# CtrlCarbinBoard_MCU.net
KiCad netlist of a schematic drawn in Altium Designer
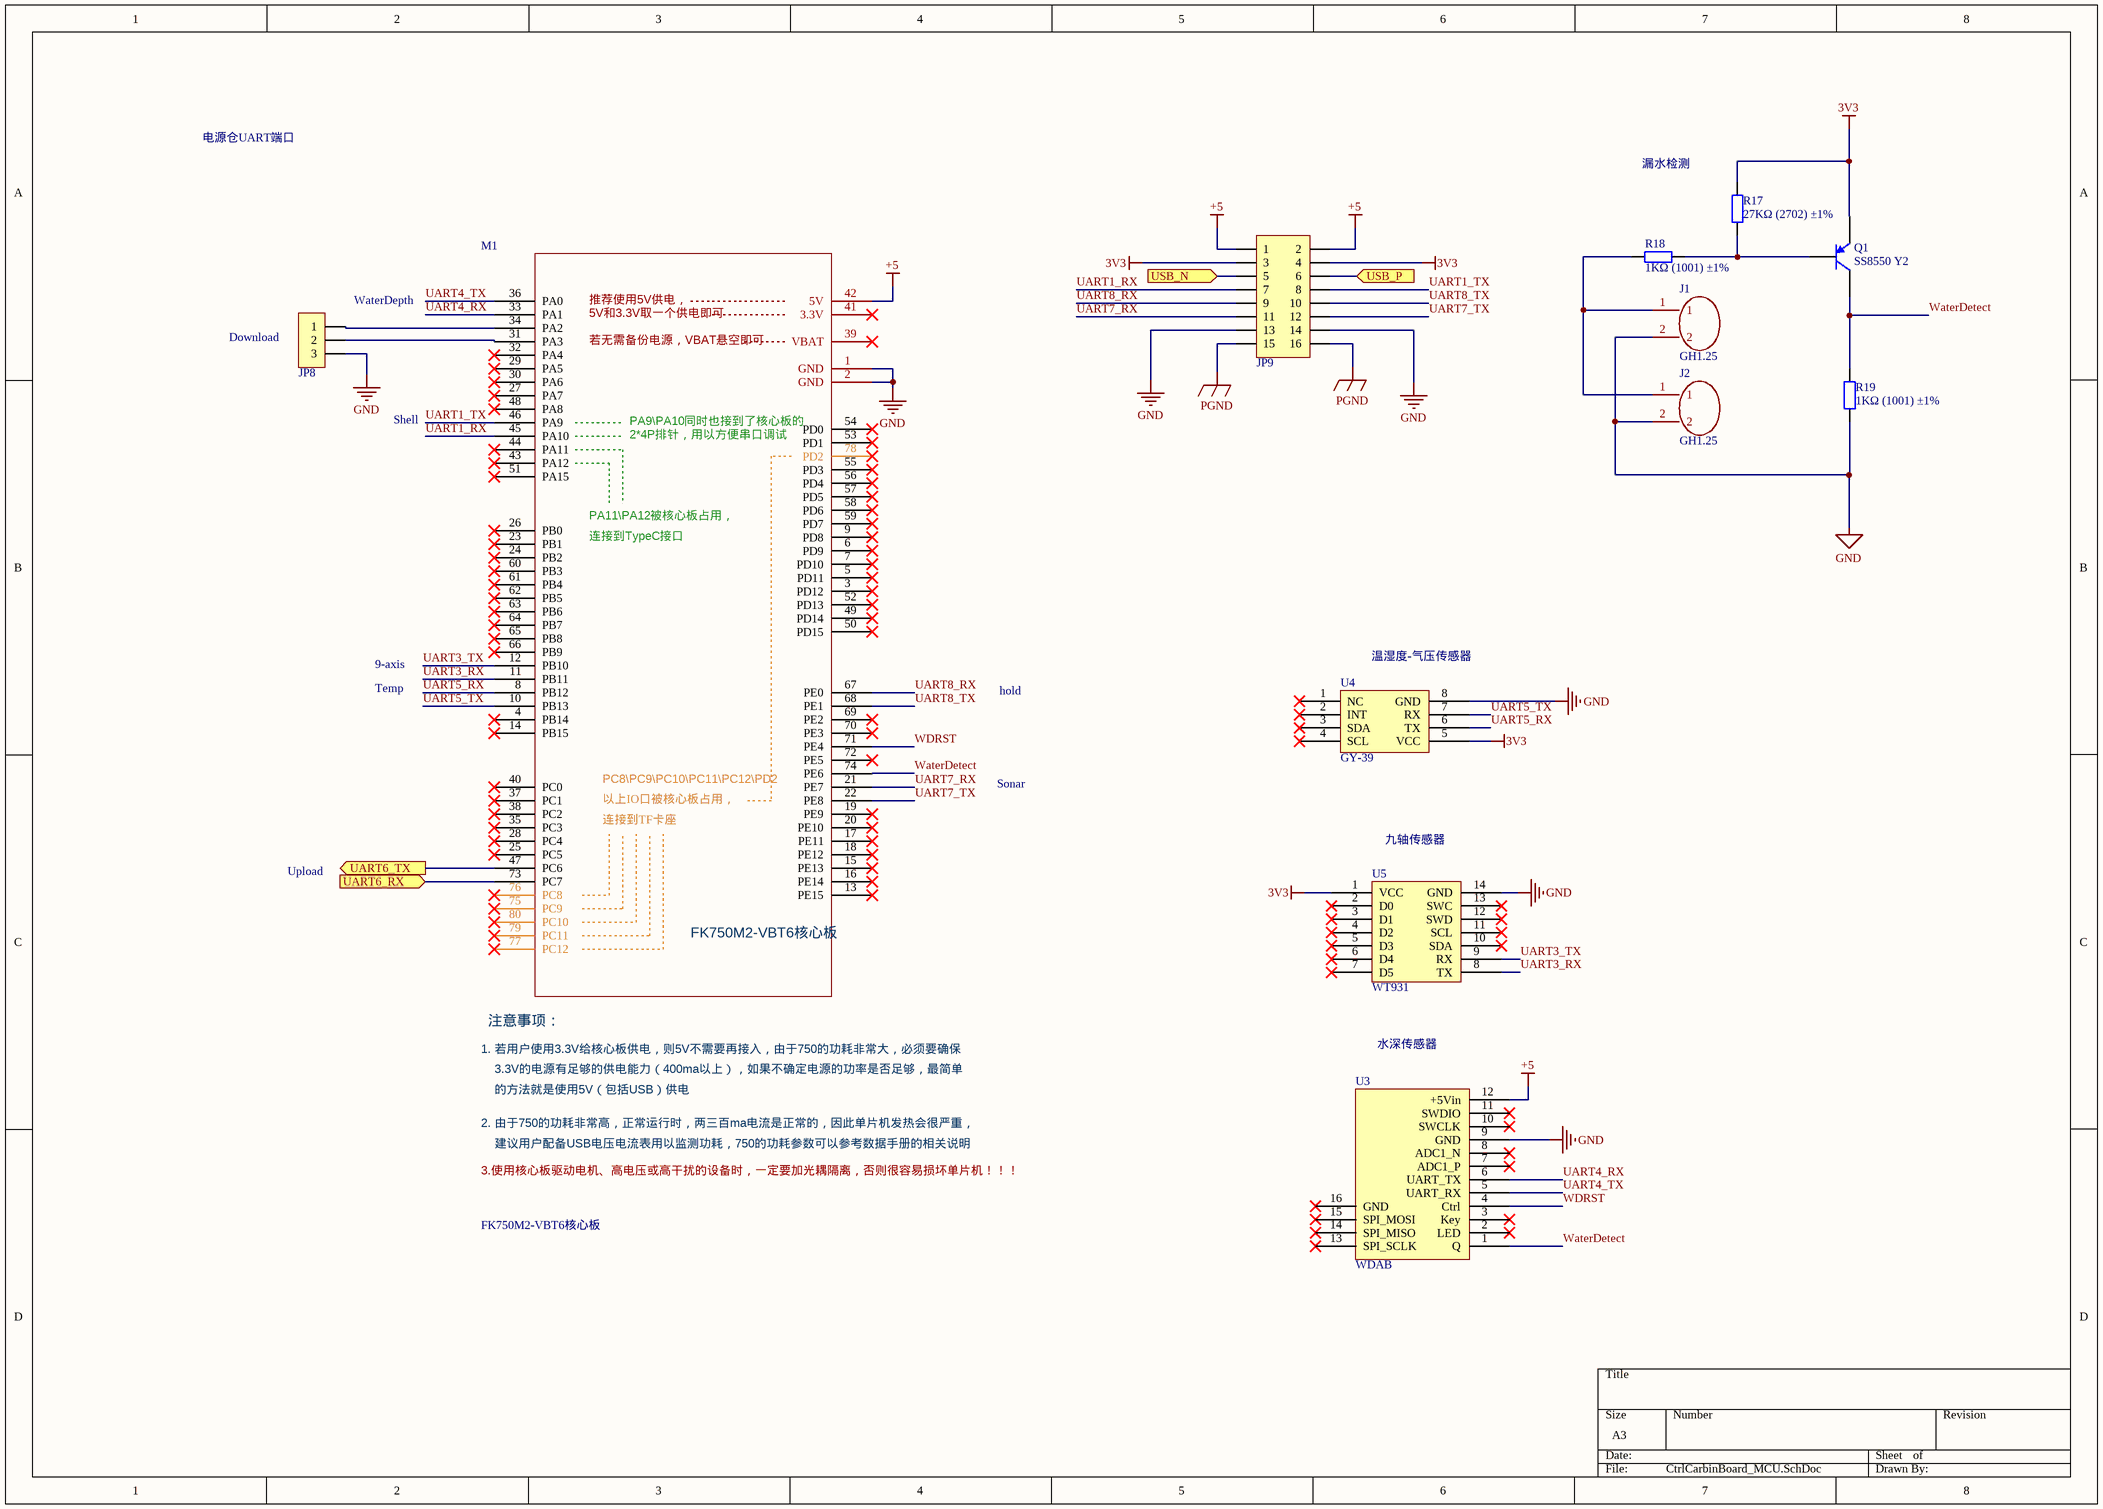
[diagram p0: CtrlCarbinBoard_MCU.SchDoc]

(export (version "E")
  (design (tool "Eeschema 10.0.6"))
  (components
    (comp (ref "J1")
      (value "GH1.25")
      (footprint "GH1.25 2pin")
      (libsource (lib "MySchLib") (part "GH1.25 2pin"))
    )
    (comp (ref "J2")
      (value "GH1.25")
      (footprint "GH1.25 2pin")
      (libsource (lib "MySchLib") (part "GH1.25 2pin"))
    )
    (comp (ref "JP8")
      (value "HDR-1X3")
      (footprint "PH2.0-LS-3P")
      (description "3P接插件")
      (fields (field (name "版权归属") "源创客"))
      (libsource (lib "4.4   - 接插件-脚距2.0") (part "Header 3"))
    )
    (comp (ref "JP9")
      (value "Header 8X2")
      (footprint "IDC2.54-LI-2x8P")
      (description "8*2P接插件")
      (fields (field (name "版权归属") "源创客"))
      (libsource (lib "4.5   - 接插件-脚距2.54") (part "Header 8X2"))
    )
    (comp (ref "M1")
      (value "FK750M2-VBT6核心板")
      (footprint "FK750M2-VBT6(精简版)")
      (libsource (lib "MySchLib") (part "FK750M2-VBT6"))
    )
    (comp (ref "Q1")
      (value "SS8550 Y2")
      (footprint "SOT-23(SOT-23-3)")
      (description "三极管")
      (libsource (lib "Miscellaneous Devices LC") (part "SOT-23 SS8550 Y2"))
    )
    (comp (ref "R17")
      (value "27KΩ (2702) ±1%")
      (footprint "0603_R")
      (description "贴片电阻")
      (libsource (lib "Miscellaneous Devices LC") (part "0603 27KΩ (2702) 1%"))
    )
    (comp (ref "R18")
      (value "1KΩ (1001) ±1%")
      (footprint "0603_R")
      (description "贴片电阻")
      (libsource (lib "") (part "0603 1KΩ (1001) 1%_1"))
    )
    (comp (ref "R19")
      (value "1KΩ (1001) ±1%")
      (footprint "0603_R")
      (description "贴片电阻")
      (libsource (lib "Miscellaneous Devices LC") (part "0603 1KΩ (1001) 1%"))
    )
    (comp (ref "U3")
      (value "WDAB")
      (footprint "WaterDepthBoard")
      (libsource (lib "MySchLib") (part "WaterDepthBoard"))
    )
    (comp (ref "U4")
      (value "GY-39")
      (footprint "GY39")
      (description "GY39温湿度大气压光照传感器")
      (libsource (lib "MySchLib") (part "GY39"))
    )
    (comp (ref "U5")
      (value "WT931")
      (footprint "WT931")
      (description "维特智能WT931九轴模块")
      (libsource (lib "MySchLib") (part "WT931"))
    )
  )
  (nets
    (net (code "1") (name "+5") (class "Default")
      (node (ref "JP9") (pin "1") (pinfunction "1_1") (pintype "passive"))
      (node (ref "JP9") (pin "2") (pinfunction "2_2") (pintype "passive"))
      (node (ref "M1") (pin "42") (pinfunction "5V_42") (pintype "passive"))
      (node (ref "U3") (pin "12") (pinfunction "+5Vin_12") (pintype "passive"))
    )
    (net (code "2") (name "/UART1_RX") (class "Default")
      (node (ref "JP9") (pin "7") (pinfunction "7_7") (pintype "passive"))
      (node (ref "M1") (pin "45") (pinfunction "PA10_45") (pintype "passive"))
    )
    (net (code "3") (name "/UART1_TX") (class "Default")
      (node (ref "JP9") (pin "8") (pinfunction "8_8") (pintype "passive"))
      (node (ref "M1") (pin "46") (pinfunction "PA9_46") (pintype "passive"))
    )
    (net (code "4") (name "/UART3_RX") (class "Default")
      (node (ref "M1") (pin "11") (pinfunction "PB11_11") (pintype "passive"))
      (node (ref "U5") (pin "8") (pinfunction "TX_8") (pintype "passive"))
    )
    (net (code "5") (name "/UART3_TX") (class "Default")
      (node (ref "M1") (pin "12") (pinfunction "PB10_12") (pintype "passive"))
      (node (ref "U5") (pin "9") (pinfunction "RX_9") (pintype "passive"))
    )
    (net (code "6") (name "/UART4_RX") (class "Default")
      (node (ref "M1") (pin "33") (pinfunction "PA1_33") (pintype "passive"))
      (node (ref "U3") (pin "6") (pinfunction "UART_TX_6") (pintype "passive"))
    )
    (net (code "7") (name "/UART4_TX") (class "Default")
      (node (ref "M1") (pin "36") (pinfunction "PA0_36") (pintype "passive"))
      (node (ref "U3") (pin "5") (pinfunction "UART_RX_5") (pintype "passive"))
    )
    (net (code "8") (name "/UART5_RX") (class "Default")
      (node (ref "M1") (pin "8") (pinfunction "PB12_8") (pintype "passive"))
      (node (ref "U4") (pin "6") (pinfunction "TX_6") (pintype "passive"))
    )
    (net (code "9") (name "/UART5_TX") (class "Default")
      (node (ref "M1") (pin "10") (pinfunction "PB13_10") (pintype "passive"))
      (node (ref "U4") (pin "7") (pinfunction "RX_7") (pintype "passive"))
    )
    (net (code "10") (name "/UART6_RX") (class "Default")
      (node (ref "M1") (pin "73") (pinfunction "PC7_73") (pintype "passive"))
    )
    (net (code "11") (name "/UART6_TX") (class "Default")
      (node (ref "M1") (pin "47") (pinfunction "PC6_47") (pintype "passive"))
    )
    (net (code "12") (name "/UART7_RX") (class "Default")
      (node (ref "JP9") (pin "11") (pinfunction "11_11") (pintype "passive"))
      (node (ref "M1") (pin "21") (pinfunction "PE7_21") (pintype "passive"))
    )
    (net (code "13") (name "/UART7_TX") (class "Default")
      (node (ref "JP9") (pin "12") (pinfunction "12_12") (pintype "passive"))
      (node (ref "M1") (pin "22") (pinfunction "PE8_22") (pintype "passive"))
    )
    (net (code "14") (name "/UART8_RX") (class "Default")
      (node (ref "JP9") (pin "9") (pinfunction "9_9") (pintype "passive"))
      (node (ref "M1") (pin "67") (pinfunction "PE0_67") (pintype "passive"))
    )
    (net (code "15") (name "/UART8_TX") (class "Default")
      (node (ref "JP9") (pin "10") (pinfunction "10_10") (pintype "passive"))
      (node (ref "M1") (pin "68") (pinfunction "PE1_68") (pintype "passive"))
    )
    (net (code "16") (name "/USB_N") (class "Default")
      (node (ref "JP9") (pin "5") (pinfunction "5_5") (pintype "passive"))
    )
    (net (code "17") (name "/USB_P") (class "Default")
      (node (ref "JP9") (pin "6") (pinfunction "6_6") (pintype "passive"))
    )
    (net (code "18") (name "/WDRST") (class "Default")
      (node (ref "M1") (pin "71") (pinfunction "PE4_71") (pintype "passive"))
      (node (ref "U3") (pin "4") (pinfunction "Ctrl_4") (pintype "passive"))
    )
    (net (code "19") (name "/WaterDetect") (class "Default")
      (node (ref "M1") (pin "74") (pinfunction "PE6_74") (pintype "passive"))
      (node (ref "Q1") (pin "3") (pinfunction "C_3") (pintype "passive"))
      (node (ref "R19") (pin "2") (pinfunction "2_2") (pintype "passive"))
      (node (ref "U3") (pin "1") (pinfunction "Q_1") (pintype "passive"))
    )
    (net (code "20") (name "3V3") (class "Default")
      (node (ref "JP9") (pin "3") (pinfunction "3_3") (pintype "passive"))
      (node (ref "JP9") (pin "4") (pinfunction "4_4") (pintype "passive"))
      (node (ref "Q1") (pin "2") (pinfunction "E_2") (pintype "passive"))
      (node (ref "R17") (pin "2") (pinfunction "2_2") (pintype "passive"))
      (node (ref "U4") (pin "5") (pinfunction "VCC_5") (pintype "passive"))
      (node (ref "U5") (pin "1") (pinfunction "VCC_1") (pintype "passive"))
    )
    (net (code "21") (name "GND") (class "Default")
      (node (ref "J1") (pin "2") (pinfunction "2_2") (pintype "passive"))
      (node (ref "J2") (pin "2") (pinfunction "2_2") (pintype "passive"))
      (node (ref "JP8") (pin "3") (pinfunction "3_3") (pintype "passive"))
      (node (ref "JP9") (pin "13") (pinfunction "13_13") (pintype "passive"))
      (node (ref "JP9") (pin "14") (pinfunction "14_14") (pintype "passive"))
      (node (ref "M1") (pin "1") (pinfunction "GND_1") (pintype "passive"))
      (node (ref "M1") (pin "2") (pinfunction "GND_2") (pintype "passive"))
      (node (ref "R19") (pin "1") (pinfunction "1_1") (pintype "passive"))
      (node (ref "U3") (pin "9") (pinfunction "GND_9") (pintype "passive"))
      (node (ref "U4") (pin "8") (pinfunction "GND_8") (pintype "passive"))
      (node (ref "U5") (pin "14") (pinfunction "GND_14") (pintype "passive"))
    )
    (net (code "22") (name "Net-(J1-Pad1)") (class "Default")
      (node (ref "J1") (pin "1") (pinfunction "1_1") (pintype "passive"))
      (node (ref "J2") (pin "1") (pinfunction "1_1") (pintype "passive"))
      (node (ref "R18") (pin "1") (pinfunction "1_1") (pintype "passive"))
    )
    (net (code "23") (name "Net-(M1-PA2)") (class "Default")
      (node (ref "JP8") (pin "1") (pinfunction "1_1") (pintype "passive"))
      (node (ref "M1") (pin "34") (pinfunction "PA2_34") (pintype "passive"))
    )
    (net (code "24") (name "Net-(M1-PA3)") (class "Default")
      (node (ref "JP8") (pin "2") (pinfunction "2_2") (pintype "passive"))
      (node (ref "M1") (pin "31") (pinfunction "PA3_31") (pintype "passive"))
    )
    (net (code "25") (name "Net-(Q1-B)") (class "Default")
      (node (ref "Q1") (pin "1") (pinfunction "B_1") (pintype "passive"))
      (node (ref "R17") (pin "1") (pinfunction "1_1") (pintype "passive"))
      (node (ref "R18") (pin "2") (pinfunction "2_2") (pintype "passive"))
    )
    (net (code "26") (name "PGND") (class "Default")
      (node (ref "JP9") (pin "15") (pinfunction "15_15") (pintype "passive"))
      (node (ref "JP9") (pin "16") (pinfunction "16_16") (pintype "passive"))
    )
    (net (code "27") (name "unconnected-(M1-3.3V-Pad41)") (class "Default")
      (node (ref "M1") (pin "41") (pinfunction "3.3V_41") (pintype "passive+no_connect"))
    )
    (net (code "28") (name "unconnected-(M1-PA4-Pad32)") (class "Default")
      (node (ref "M1") (pin "32") (pinfunction "PA4_32") (pintype "passive+no_connect"))
    )
    (net (code "29") (name "unconnected-(M1-PA5-Pad29)") (class "Default")
      (node (ref "M1") (pin "29") (pinfunction "PA5_29") (pintype "passive+no_connect"))
    )
    (net (code "30") (name "unconnected-(M1-PA6-Pad30)") (class "Default")
      (node (ref "M1") (pin "30") (pinfunction "PA6_30") (pintype "passive+no_connect"))
    )
    (net (code "31") (name "unconnected-(M1-PA7-Pad27)") (class "Default")
      (node (ref "M1") (pin "27") (pinfunction "PA7_27") (pintype "passive+no_connect"))
    )
    (net (code "32") (name "unconnected-(M1-PA8-Pad48)") (class "Default")
      (node (ref "M1") (pin "48") (pinfunction "PA8_48") (pintype "passive+no_connect"))
    )
    (net (code "33") (name "unconnected-(M1-PA11-Pad44)") (class "Default")
      (node (ref "M1") (pin "44") (pinfunction "PA11_44") (pintype "passive+no_connect"))
    )
    (net (code "34") (name "unconnected-(M1-PA12-Pad43)") (class "Default")
      (node (ref "M1") (pin "43") (pinfunction "PA12_43") (pintype "passive+no_connect"))
    )
    (net (code "35") (name "unconnected-(M1-PA15-Pad51)") (class "Default")
      (node (ref "M1") (pin "51") (pinfunction "PA15_51") (pintype "passive+no_connect"))
    )
    (net (code "36") (name "unconnected-(M1-PB0-Pad26)") (class "Default")
      (node (ref "M1") (pin "26") (pinfunction "PB0_26") (pintype "passive+no_connect"))
    )
    (net (code "37") (name "unconnected-(M1-PB1-Pad23)") (class "Default")
      (node (ref "M1") (pin "23") (pinfunction "PB1_23") (pintype "passive+no_connect"))
    )
    (net (code "38") (name "unconnected-(M1-PB2-Pad24)") (class "Default")
      (node (ref "M1") (pin "24") (pinfunction "PB2_24") (pintype "passive+no_connect"))
    )
    (net (code "39") (name "unconnected-(M1-PB3-Pad60)") (class "Default")
      (node (ref "M1") (pin "60") (pinfunction "PB3_60") (pintype "passive+no_connect"))
    )
    (net (code "40") (name "unconnected-(M1-PB4-Pad61)") (class "Default")
      (node (ref "M1") (pin "61") (pinfunction "PB4_61") (pintype "passive+no_connect"))
    )
    (net (code "41") (name "unconnected-(M1-PB5-Pad62)") (class "Default")
      (node (ref "M1") (pin "62") (pinfunction "PB5_62") (pintype "passive+no_connect"))
    )
    (net (code "42") (name "unconnected-(M1-PB6-Pad63)") (class "Default")
      (node (ref "M1") (pin "63") (pinfunction "PB6_63") (pintype "passive+no_connect"))
    )
    (net (code "43") (name "unconnected-(M1-PB7-Pad64)") (class "Default")
      (node (ref "M1") (pin "64") (pinfunction "PB7_64") (pintype "passive+no_connect"))
    )
    (net (code "44") (name "unconnected-(M1-PB8-Pad65)") (class "Default")
      (node (ref "M1") (pin "65") (pinfunction "PB8_65") (pintype "passive+no_connect"))
    )
    (net (code "45") (name "unconnected-(M1-PB9-Pad66)") (class "Default")
      (node (ref "M1") (pin "66") (pinfunction "PB9_66") (pintype "passive+no_connect"))
    )
    (net (code "46") (name "unconnected-(M1-PB14-Pad4)") (class "Default")
      (node (ref "M1") (pin "4") (pinfunction "PB14_4") (pintype "passive+no_connect"))
    )
    (net (code "47") (name "unconnected-(M1-PB15-Pad14)") (class "Default")
      (node (ref "M1") (pin "14") (pinfunction "PB15_14") (pintype "passive+no_connect"))
    )
    (net (code "48") (name "unconnected-(M1-PC0-Pad40)") (class "Default")
      (node (ref "M1") (pin "40") (pinfunction "PC0_40") (pintype "passive+no_connect"))
    )
    (net (code "49") (name "unconnected-(M1-PC1-Pad37)") (class "Default")
      (node (ref "M1") (pin "37") (pinfunction "PC1_37") (pintype "passive+no_connect"))
    )
    (net (code "50") (name "unconnected-(M1-PC2-Pad38)") (class "Default")
      (node (ref "M1") (pin "38") (pinfunction "PC2_38") (pintype "passive+no_connect"))
    )
    (net (code "51") (name "unconnected-(M1-PC3-Pad35)") (class "Default")
      (node (ref "M1") (pin "35") (pinfunction "PC3_35") (pintype "passive+no_connect"))
    )
    (net (code "52") (name "unconnected-(M1-PC4-Pad28)") (class "Default")
      (node (ref "M1") (pin "28") (pinfunction "PC4_28") (pintype "passive+no_connect"))
    )
    (net (code "53") (name "unconnected-(M1-PC5-Pad25)") (class "Default")
      (node (ref "M1") (pin "25") (pinfunction "PC5_25") (pintype "passive+no_connect"))
    )
    (net (code "54") (name "unconnected-(M1-PC8-Pad76)") (class "Default")
      (node (ref "M1") (pin "76") (pinfunction "PC8_76") (pintype "passive+no_connect"))
    )
    (net (code "55") (name "unconnected-(M1-PC9-Pad75)") (class "Default")
      (node (ref "M1") (pin "75") (pinfunction "PC9_75") (pintype "passive+no_connect"))
    )
    (net (code "56") (name "unconnected-(M1-PC10-Pad80)") (class "Default")
      (node (ref "M1") (pin "80") (pinfunction "PC10_80") (pintype "passive+no_connect"))
    )
    (net (code "57") (name "unconnected-(M1-PC11-Pad79)") (class "Default")
      (node (ref "M1") (pin "79") (pinfunction "PC11_79") (pintype "passive+no_connect"))
    )
    (net (code "58") (name "unconnected-(M1-PC12-Pad77)") (class "Default")
      (node (ref "M1") (pin "77") (pinfunction "PC12_77") (pintype "passive+no_connect"))
    )
    (net (code "59") (name "unconnected-(M1-PD0-Pad54)") (class "Default")
      (node (ref "M1") (pin "54") (pinfunction "PD0_54") (pintype "passive+no_connect"))
    )
    (net (code "60") (name "unconnected-(M1-PD1-Pad53)") (class "Default")
      (node (ref "M1") (pin "53") (pinfunction "PD1_53") (pintype "passive+no_connect"))
    )
    (net (code "61") (name "unconnected-(M1-PD2-Pad78)") (class "Default")
      (node (ref "M1") (pin "78") (pinfunction "PD2_78") (pintype "passive+no_connect"))
    )
    (net (code "62") (name "unconnected-(M1-PD3-Pad55)") (class "Default")
      (node (ref "M1") (pin "55") (pinfunction "PD3_55") (pintype "passive+no_connect"))
    )
    (net (code "63") (name "unconnected-(M1-PD4-Pad56)") (class "Default")
      (node (ref "M1") (pin "56") (pinfunction "PD4_56") (pintype "passive+no_connect"))
    )
    (net (code "64") (name "unconnected-(M1-PD5-Pad57)") (class "Default")
      (node (ref "M1") (pin "57") (pinfunction "PD5_57") (pintype "passive+no_connect"))
    )
    (net (code "65") (name "unconnected-(M1-PD6-Pad58)") (class "Default")
      (node (ref "M1") (pin "58") (pinfunction "PD6_58") (pintype "passive+no_connect"))
    )
    (net (code "66") (name "unconnected-(M1-PD7-Pad59)") (class "Default")
      (node (ref "M1") (pin "59") (pinfunction "PD7_59") (pintype "passive+no_connect"))
    )
    (net (code "67") (name "unconnected-(M1-PD8-Pad9)") (class "Default")
      (node (ref "M1") (pin "9") (pinfunction "PD8_9") (pintype "passive+no_connect"))
    )
    (net (code "68") (name "unconnected-(M1-PD9-Pad6)") (class "Default")
      (node (ref "M1") (pin "6") (pinfunction "PD9_6") (pintype "passive+no_connect"))
    )
    (net (code "69") (name "unconnected-(M1-PD10-Pad7)") (class "Default")
      (node (ref "M1") (pin "7") (pinfunction "PD10_7") (pintype "passive+no_connect"))
    )
    (net (code "70") (name "unconnected-(M1-PD11-Pad5)") (class "Default")
      (node (ref "M1") (pin "5") (pinfunction "PD11_5") (pintype "passive+no_connect"))
    )
    (net (code "71") (name "unconnected-(M1-PD12-Pad3)") (class "Default")
      (node (ref "M1") (pin "3") (pinfunction "PD12_3") (pintype "passive+no_connect"))
    )
    (net (code "72") (name "unconnected-(M1-PD13-Pad52)") (class "Default")
      (node (ref "M1") (pin "52") (pinfunction "PD13_52") (pintype "passive+no_connect"))
    )
    (net (code "73") (name "unconnected-(M1-PD14-Pad49)") (class "Default")
      (node (ref "M1") (pin "49") (pinfunction "PD14_49") (pintype "passive+no_connect"))
    )
    (net (code "74") (name "unconnected-(M1-PD15-Pad50)") (class "Default")
      (node (ref "M1") (pin "50") (pinfunction "PD15_50") (pintype "passive+no_connect"))
    )
    (net (code "75") (name "unconnected-(M1-PE2-Pad69)") (class "Default")
      (node (ref "M1") (pin "69") (pinfunction "PE2_69") (pintype "passive+no_connect"))
    )
    (net (code "76") (name "unconnected-(M1-PE3-Pad70)") (class "Default")
      (node (ref "M1") (pin "70") (pinfunction "PE3_70") (pintype "passive+no_connect"))
    )
    (net (code "77") (name "unconnected-(M1-PE5-Pad72)") (class "Default")
      (node (ref "M1") (pin "72") (pinfunction "PE5_72") (pintype "passive+no_connect"))
    )
    (net (code "78") (name "unconnected-(M1-PE9-Pad19)") (class "Default")
      (node (ref "M1") (pin "19") (pinfunction "PE9_19") (pintype "passive+no_connect"))
    )
    (net (code "79") (name "unconnected-(M1-PE10-Pad20)") (class "Default")
      (node (ref "M1") (pin "20") (pinfunction "PE10_20") (pintype "passive+no_connect"))
    )
    (net (code "80") (name "unconnected-(M1-PE11-Pad17)") (class "Default")
      (node (ref "M1") (pin "17") (pinfunction "PE11_17") (pintype "passive+no_connect"))
    )
    (net (code "81") (name "unconnected-(M1-PE12-Pad18)") (class "Default")
      (node (ref "M1") (pin "18") (pinfunction "PE12_18") (pintype "passive+no_connect"))
    )
    (net (code "82") (name "unconnected-(M1-PE13-Pad15)") (class "Default")
      (node (ref "M1") (pin "15") (pinfunction "PE13_15") (pintype "passive+no_connect"))
    )
    (net (code "83") (name "unconnected-(M1-PE14-Pad16)") (class "Default")
      (node (ref "M1") (pin "16") (pinfunction "PE14_16") (pintype "passive+no_connect"))
    )
    (net (code "84") (name "unconnected-(M1-PE15-Pad13)") (class "Default")
      (node (ref "M1") (pin "13") (pinfunction "PE15_13") (pintype "passive+no_connect"))
    )
    (net (code "85") (name "unconnected-(M1-VBAT-Pad39)") (class "Default")
      (node (ref "M1") (pin "39") (pinfunction "VBAT_39") (pintype "passive+no_connect"))
    )
    (net (code "86") (name "unconnected-(U3-ADC1_N-Pad8)") (class "Default")
      (node (ref "U3") (pin "8") (pinfunction "ADC1_N_8") (pintype "passive+no_connect"))
    )
    (net (code "87") (name "unconnected-(U3-ADC1_P-Pad7)") (class "Default")
      (node (ref "U3") (pin "7") (pinfunction "ADC1_P_7") (pintype "passive+no_connect"))
    )
    (net (code "88") (name "unconnected-(U3-GND-Pad16)") (class "Default")
      (node (ref "U3") (pin "16") (pinfunction "GND_16") (pintype "passive+no_connect"))
    )
    (net (code "89") (name "unconnected-(U3-Key-Pad3)") (class "Default")
      (node (ref "U3") (pin "3") (pinfunction "Key_3") (pintype "passive+no_connect"))
    )
    (net (code "90") (name "unconnected-(U3-LED-Pad2)") (class "Default")
      (node (ref "U3") (pin "2") (pinfunction "LED_2") (pintype "passive+no_connect"))
    )
    (net (code "91") (name "unconnected-(U3-SPI_MISO-Pad14)") (class "Default")
      (node (ref "U3") (pin "14") (pinfunction "SPI_MISO_14") (pintype "passive+no_connect"))
    )
    (net (code "92") (name "unconnected-(U3-SPI_MOSI-Pad15)") (class "Default")
      (node (ref "U3") (pin "15") (pinfunction "SPI_MOSI_15") (pintype "passive+no_connect"))
    )
    (net (code "93") (name "unconnected-(U3-SPI_SCLK-Pad13)") (class "Default")
      (node (ref "U3") (pin "13") (pinfunction "SPI_SCLK_13") (pintype "passive+no_connect"))
    )
    (net (code "94") (name "unconnected-(U3-SWCLK-Pad10)") (class "Default")
      (node (ref "U3") (pin "10") (pinfunction "SWCLK_10") (pintype "passive+no_connect"))
    )
    (net (code "95") (name "unconnected-(U3-SWDIO-Pad11)") (class "Default")
      (node (ref "U3") (pin "11") (pinfunction "SWDIO_11") (pintype "passive+no_connect"))
    )
    (net (code "96") (name "unconnected-(U4-INT-Pad2)") (class "Default")
      (node (ref "U4") (pin "2") (pinfunction "INT_2") (pintype "passive+no_connect"))
    )
    (net (code "97") (name "unconnected-(U4-NC-Pad1)") (class "Default")
      (node (ref "U4") (pin "1") (pinfunction "NC_1") (pintype "passive+no_connect"))
    )
    (net (code "98") (name "unconnected-(U4-SCL-Pad4)") (class "Default")
      (node (ref "U4") (pin "4") (pinfunction "SCL_4") (pintype "passive+no_connect"))
    )
    (net (code "99") (name "unconnected-(U4-SDA-Pad3)") (class "Default")
      (node (ref "U4") (pin "3") (pinfunction "SDA_3") (pintype "passive+no_connect"))
    )
    (net (code "100") (name "unconnected-(U5-D0-Pad2)") (class "Default")
      (node (ref "U5") (pin "2") (pinfunction "D0_2") (pintype "passive+no_connect"))
    )
    (net (code "101") (name "unconnected-(U5-D1-Pad3)") (class "Default")
      (node (ref "U5") (pin "3") (pinfunction "D1_3") (pintype "passive+no_connect"))
    )
    (net (code "102") (name "unconnected-(U5-D2-Pad4)") (class "Default")
      (node (ref "U5") (pin "4") (pinfunction "D2_4") (pintype "passive+no_connect"))
    )
    (net (code "103") (name "unconnected-(U5-D3-Pad5)") (class "Default")
      (node (ref "U5") (pin "5") (pinfunction "D3_5") (pintype "passive+no_connect"))
    )
    (net (code "104") (name "unconnected-(U5-D4-Pad6)") (class "Default")
      (node (ref "U5") (pin "6") (pinfunction "D4_6") (pintype "passive+no_connect"))
    )
    (net (code "105") (name "unconnected-(U5-D5-Pad7)") (class "Default")
      (node (ref "U5") (pin "7") (pinfunction "D5_7") (pintype "passive+no_connect"))
    )
    (net (code "106") (name "unconnected-(U5-SCL-Pad11)") (class "Default")
      (node (ref "U5") (pin "11") (pinfunction "SCL_11") (pintype "passive+no_connect"))
    )
    (net (code "107") (name "unconnected-(U5-SDA-Pad10)") (class "Default")
      (node (ref "U5") (pin "10") (pinfunction "SDA_10") (pintype "passive+no_connect"))
    )
    (net (code "108") (name "unconnected-(U5-SWC-Pad13)") (class "Default")
      (node (ref "U5") (pin "13") (pinfunction "SWC_13") (pintype "passive+no_connect"))
    )
    (net (code "109") (name "unconnected-(U5-SWD-Pad12)") (class "Default")
      (node (ref "U5") (pin "12") (pinfunction "SWD_12") (pintype "passive+no_connect"))
    )
  )
)
